# Power_Supply.net
KiCad netlist of a schematic drawn in Altium Designer
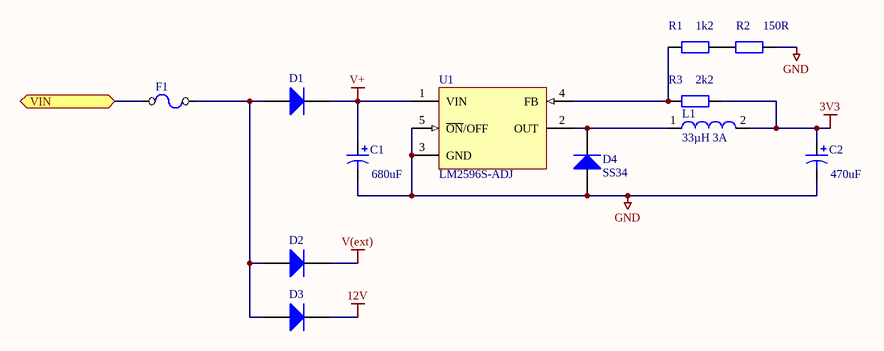
[diagram p0: Power Supply.SchDoc]

(export (version "E")
  (design (tool "Eeschema 10.0.6"))
  (components
    (comp (ref "C1")
      (value "680uF")
      (footprint "PCB-jznsty645daf9i4vncxx-1")
      (description "Capacitor Electrolytic E-Case (8mm Diameter)")
      (libsource (lib "CommunityVault") (part "CMP-jznsty645daf9i4vncxx-1"))
    )
    (comp (ref "C2")
      (value "470uF")
      (footprint "PCB-jznsty645daf9i4vncxx-1")
      (description "Capacitor Electrolytic E-Case (8mm Diameter)")
      (libsource (lib "CommunityVault") (part "CMP-jznsty645daf9i4vncxx-1"))
    )
    (comp (ref "D1")
      (value "Vishay / Semiconductors S1MHE3/61T")
      (footprint "ONSC-SMA-2-403D-02_V")
      (description "DIODE GPP 1A 1000V SMA DO-214AC")
      (fields (field (name "MANUFACTURER PART NUMBER") "S1MHE3/61T") (field (name "MANUFACTURER") "Vishay"))
      (libsource (lib "FavoritesLibrary") (part "DIOD-D-A1K2-2"))
    )
    (comp (ref "D2")
      (value "Vishay / Semiconductors S1MHE3/61T")
      (footprint "ONSC-SMA-2-403D-02_V")
      (description "DIODE GPP 1A 1000V SMA DO-214AC")
      (fields (field (name "MANUFACTURER PART NUMBER") "S1MHE3/61T") (field (name "MANUFACTURER") "Vishay"))
      (libsource (lib "FavoritesLibrary") (part "DIOD-D-A1K2-2"))
    )
    (comp (ref "D3")
      (value "Vishay / Semiconductors S1MHE3/61T")
      (footprint "ONSC-SMA-2-403D-02_V")
      (description "DIODE GPP 1A 1000V SMA DO-214AC")
      (fields (field (name "MANUFACTURER PART NUMBER") "S1MHE3/61T") (field (name "MANUFACTURER") "Vishay"))
      (libsource (lib "FavoritesLibrary") (part "DIOD-D-A1K2-2"))
    )
    (comp (ref "D4")
      (value "SS34")
      (footprint "PCB-16344855-1")
      (description "DIODE SCHOTTKY 40V 3A SMC")
      (libsource (lib "FavoritesLibrary") (part "SYM-16344855-1"))
    )
    (comp (ref "F1")
      (value "1210L110/12WR")
      (footprint "PCB-8881447-1")
      (description "PTC 12V POLYFUSE SMT 1210 1.10A")
      (fields (field (name "MANUFACTURER") "Littelfuse"))
      (libsource (lib "CommunityVault") (part "SYM-8881447-1"))
    )
    (comp (ref "L1")
      (value "33µH 3A")
      (footprint "WE-PD-L")
      (description "SMD POWER INDUCTOR 12 x 12 mm")
      (libsource (lib "FavoritesLibrary") (part "PAS-IND-INDUCTOR-2"))
    )
    (comp (ref "R1")
      (value "1k2")
      (footprint "PCB-3652081-2")
      (description "GENERIC 0805 RESISTOR")
      (libsource (lib "FavoritesLibrary") (part "SYM-rprrpiwz7au7w5x5ojb2-1"))
    )
    (comp (ref "R2")
      (value "150R")
      (footprint "PCB-3652081-2")
      (description "GENERIC 0805 RESISTOR")
      (libsource (lib "FavoritesLibrary") (part "SYM-rprrpiwz7au7w5x5ojb2-1"))
    )
    (comp (ref "R3")
      (value "2k2")
      (footprint "PCB-3652081-2")
      (description "GENERIC 0805 RESISTOR")
      (libsource (lib "FavoritesLibrary") (part "SYM-rprrpiwz7au7w5x5ojb2-1"))
    )
    (comp (ref "U1")
      (value "LM2596S-ADJ")
      (footprint "TS5B_L")
      (description "SIMPLE SWITCHER® Power Converter 150 KHz 3A Step-Down Voltage Regulator, 5-pin TO-263")
      (fields (field (name "MANUFACTURER") "TI (Texas Instruments) / National Semiconductor"))
      (libsource (lib "FavoritesLibrary") (part "PM-REG-LM2575HVS-12"))
    )
  )
  (nets
    (net (code "1") (name "/VIN") (class "Default")
      (node (ref "F1") (pin "1") (pinfunction "1_1") (pintype "passive"))
    )
    (net (code "2") (name "3V3") (class "Default")
      (node (ref "C2") (pin "1") (pinfunction "1_1") (pintype "passive"))
      (node (ref "L1") (pin "2") (pinfunction "2_2") (pintype "passive"))
      (node (ref "R3") (pin "2") (pinfunction "2_2") (pintype "passive"))
    )
    (net (code "3") (name "12V") (class "Default")
      (node (ref "D3") (pin "2") (pinfunction "K_2") (pintype "passive"))
    )
    (net (code "4") (name "GND") (class "Default")
      (node (ref "C1") (pin "2") (pinfunction "2_2") (pintype "passive"))
      (node (ref "C2") (pin "2") (pinfunction "2_2") (pintype "passive"))
      (node (ref "D4") (pin "1") (pinfunction "A_1") (pintype "passive"))
      (node (ref "R2") (pin "2") (pinfunction "2_2") (pintype "passive"))
      (node (ref "U1") (pin "3") (pinfunction "GND_3") (pintype "power_in"))
      (node (ref "U1") (pin "5") (pinfunction "~{ON}/OFF_5") (pintype "input"))
    )
    (net (code "5") (name "Net-(D1-A)") (class "Default")
      (node (ref "D1") (pin "1") (pinfunction "A_1") (pintype "passive"))
      (node (ref "D2") (pin "1") (pinfunction "A_1") (pintype "passive"))
      (node (ref "D3") (pin "1") (pinfunction "A_1") (pintype "passive"))
      (node (ref "F1") (pin "2") (pinfunction "2_2") (pintype "passive"))
    )
    (net (code "6") (name "Net-(D4-K)") (class "Default")
      (node (ref "D4") (pin "2") (pinfunction "K_2") (pintype "passive"))
      (node (ref "L1") (pin "1") (pinfunction "1_1") (pintype "passive"))
      (node (ref "U1") (pin "2") (pinfunction "OUT_2") (pintype "power_in"))
    )
    (net (code "7") (name "Net-(R1-Pad2)") (class "Default")
      (node (ref "R1") (pin "2") (pinfunction "2_2") (pintype "passive"))
      (node (ref "R2") (pin "1") (pinfunction "1_1") (pintype "passive"))
    )
    (net (code "8") (name "Net-(U1-FB)") (class "Default")
      (node (ref "R1") (pin "1") (pinfunction "1_1") (pintype "passive"))
      (node (ref "R3") (pin "1") (pinfunction "1_1") (pintype "passive"))
      (node (ref "U1") (pin "4") (pinfunction "FB_4") (pintype "input"))
    )
    (net (code "9") (name "V(ext)") (class "Default")
      (node (ref "D2") (pin "2") (pinfunction "K_2") (pintype "passive"))
    )
    (net (code "10") (name "V+") (class "Default")
      (node (ref "C1") (pin "1") (pinfunction "1_1") (pintype "passive"))
      (node (ref "D1") (pin "2") (pinfunction "K_2") (pintype "passive"))
      (node (ref "U1") (pin "1") (pinfunction "VIN_1") (pintype "power_in"))
    )
  )
)
